# PROGRAMMING.net
KiCad netlist of a schematic drawn in Altium Designer
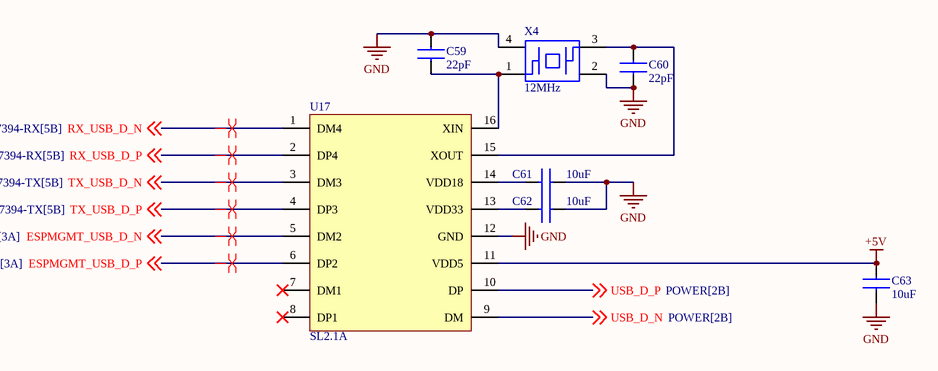
[diagram p0: PROGRAMMING.SchDoc]

(export (version "E")
  (design (tool "Eeschema 10.0.6"))
  (components
    (comp (ref "C59")
      (value "22pF")
      (footprint "CAP_0402")
      (description "MULTILAYER CERAMIC CAPACITORS MLCC - SMD/SMT 22PF 50V 0402 ROHS 0402CG220J500NT")
      (fields (field (name "MFR PART #") "0402CG220J500NT") (field (name "LCSC PART#") "C1555"))
      (libsource (lib "LotusSound") (part "CAP_0402CG220J500NT"))
    )
    (comp (ref "C60")
      (value "22pF")
      (footprint "CAP_0402")
      (description "MULTILAYER CERAMIC CAPACITORS MLCC - SMD/SMT 22PF 50V 0402 ROHS 0402CG220J500NT")
      (fields (field (name "MFR PART #") "0402CG220J500NT") (field (name "LCSC PART#") "C1555"))
      (libsource (lib "LotusSound") (part "CAP_0402CG220J500NT"))
    )
    (comp (ref "C61")
      (value "10uF")
      (footprint "CAP_0402")
      (description "Cap Ceramic 10uF 6.3V X5R 20% SMD 0402 85°C Paper T/R")
      (fields
        (field (name "MANUFACTURER") "Samsung")
        (field (name "MANUFACTURER PART NUMBER") "CL05A106MQ5NUNC")
      )
      (libsource (lib "LotusSound") (part "CAP_CL05A106MQ5NUNC"))
    )
    (comp (ref "C62")
      (value "10uF")
      (footprint "CAP_0402")
      (description "Cap Ceramic 10uF 6.3V X5R 20% SMD 0402 85°C Paper T/R")
      (fields
        (field (name "MANUFACTURER") "Samsung")
        (field (name "MANUFACTURER PART NUMBER") "CL05A106MQ5NUNC")
      )
      (libsource (lib "LotusSound") (part "CAP_CL05A106MQ5NUNC"))
    )
    (comp (ref "C63")
      (value "10uF")
      (footprint "CAP_0402")
      (description "Cap Ceramic 10uF 6.3V X5R 20% SMD 0402 85°C Paper T/R")
      (fields
        (field (name "MANUFACTURER") "Samsung")
        (field (name "MANUFACTURER PART NUMBER") "CL05A106MQ5NUNC")
      )
      (libsource (lib "LotusSound") (part "CAP_CL05A106MQ5NUNC"))
    )
    (comp (ref "U17")
      (value "SL2.1A")
      (footprint "IC_SL2.1A")
      (description "USB 2.0 HIGH SPEED 4-PORT HUB CONTROLLER")
      (fields (field (name "MF") "CoreChips ShenZhen CO.,Ltd"))
      (libsource (lib "LotusSound") (part "IC_SL2.1A"))
    )
    (comp (ref "X4")
      (value "12MHz")
      (footprint "XTAL_TAXM12M4RLBDDT2T")
      (fields
        (field (name "MANUFACTURER") "TAE(Zhejiang Abel Elec)")
        (field (name "MANUFACTURER PART NUMBER") "TAXM12M4RLBDDT2T")
      )
      (libsource (lib "LotusSound") (part "XTAL_TAXM12M4RLBDDT2T"))
    )
  )
  (nets
    (net (code "1") (name "+5V") (class "Default")
      (node (ref "C63") (pin "2") (pinfunction "2_2") (pintype "passive"))
      (node (ref "U17") (pin "11") (pinfunction "VDD5_11") (pintype "passive"))
    )
    (net (code "2") (name "ESPMGMT_USB_D_N") (class "Default")
      (node (ref "U17") (pin "5") (pinfunction "DM2_5") (pintype "passive"))
    )
    (net (code "3") (name "ESPMGMT_USB_D_P") (class "Default")
      (node (ref "U17") (pin "6") (pinfunction "DP2_6") (pintype "passive"))
    )
    (net (code "4") (name "GND") (class "Default")
      (node (ref "C59") (pin "2") (pinfunction "2_2") (pintype "passive"))
      (node (ref "C60") (pin "1") (pinfunction "1_1") (pintype "passive"))
      (node (ref "C61") (pin "2") (pinfunction "2_2") (pintype "passive"))
      (node (ref "C62") (pin "2") (pinfunction "2_2") (pintype "passive"))
      (node (ref "C63") (pin "1") (pinfunction "1_1") (pintype "passive"))
      (node (ref "U17") (pin "12") (pinfunction "GND_12") (pintype "passive"))
      (node (ref "X4") (pin "2") (pinfunction "GND_2") (pintype "power_in"))
      (node (ref "X4") (pin "4") (pinfunction "4_4") (pintype "passive"))
    )
    (net (code "5") (name "Net-(U17-VDD18)") (class "Default")
      (node (ref "C61") (pin "1") (pinfunction "1_1") (pintype "passive"))
      (node (ref "U17") (pin "14") (pinfunction "VDD18_14") (pintype "passive"))
    )
    (net (code "6") (name "Net-(U17-VDD33)") (class "Default")
      (node (ref "C62") (pin "1") (pinfunction "1_1") (pintype "passive"))
      (node (ref "U17") (pin "13") (pinfunction "VDD33_13") (pintype "passive"))
    )
    (net (code "7") (name "Net-(U17-XIN)") (class "Default")
      (node (ref "C59") (pin "1") (pinfunction "1_1") (pintype "passive"))
      (node (ref "U17") (pin "16") (pinfunction "XIN_16") (pintype "passive"))
      (node (ref "X4") (pin "1") (pinfunction "IN/OUT_1") (pintype "passive"))
    )
    (net (code "8") (name "Net-(U17-XOUT)") (class "Default")
      (node (ref "C60") (pin "2") (pinfunction "2_2") (pintype "passive"))
      (node (ref "U17") (pin "15") (pinfunction "XOUT_15") (pintype "passive"))
      (node (ref "X4") (pin "3") (pinfunction "3_3") (pintype "passive"))
    )
    (net (code "9") (name "RX_USB_D_N") (class "Default")
      (node (ref "U17") (pin "1") (pinfunction "DM4_1") (pintype "passive"))
    )
    (net (code "10") (name "RX_USB_D_P") (class "Default")
      (node (ref "U17") (pin "2") (pinfunction "DP4_2") (pintype "passive"))
    )
    (net (code "11") (name "TX_USB_D_N") (class "Default")
      (node (ref "U17") (pin "3") (pinfunction "DM3_3") (pintype "passive"))
    )
    (net (code "12") (name "TX_USB_D_P") (class "Default")
      (node (ref "U17") (pin "4") (pinfunction "DP3_4") (pintype "passive"))
    )
    (net (code "13") (name "USB_D_N") (class "Default")
      (node (ref "U17") (pin "9") (pinfunction "DM_9") (pintype "passive"))
    )
    (net (code "14") (name "USB_D_P") (class "Default")
      (node (ref "U17") (pin "10") (pinfunction "DP_10") (pintype "passive"))
    )
    (net (code "15") (name "unconnected-(U17-DM1-Pad7)") (class "Default")
      (node (ref "U17") (pin "7") (pinfunction "DM1_7") (pintype "passive+no_connect"))
    )
    (net (code "16") (name "unconnected-(U17-DP1-Pad8)") (class "Default")
      (node (ref "U17") (pin "8") (pinfunction "DP1_8") (pintype "passive+no_connect"))
    )
  )
)
